# TopView.net
KiCad netlist of a schematic drawn in Altium Designer
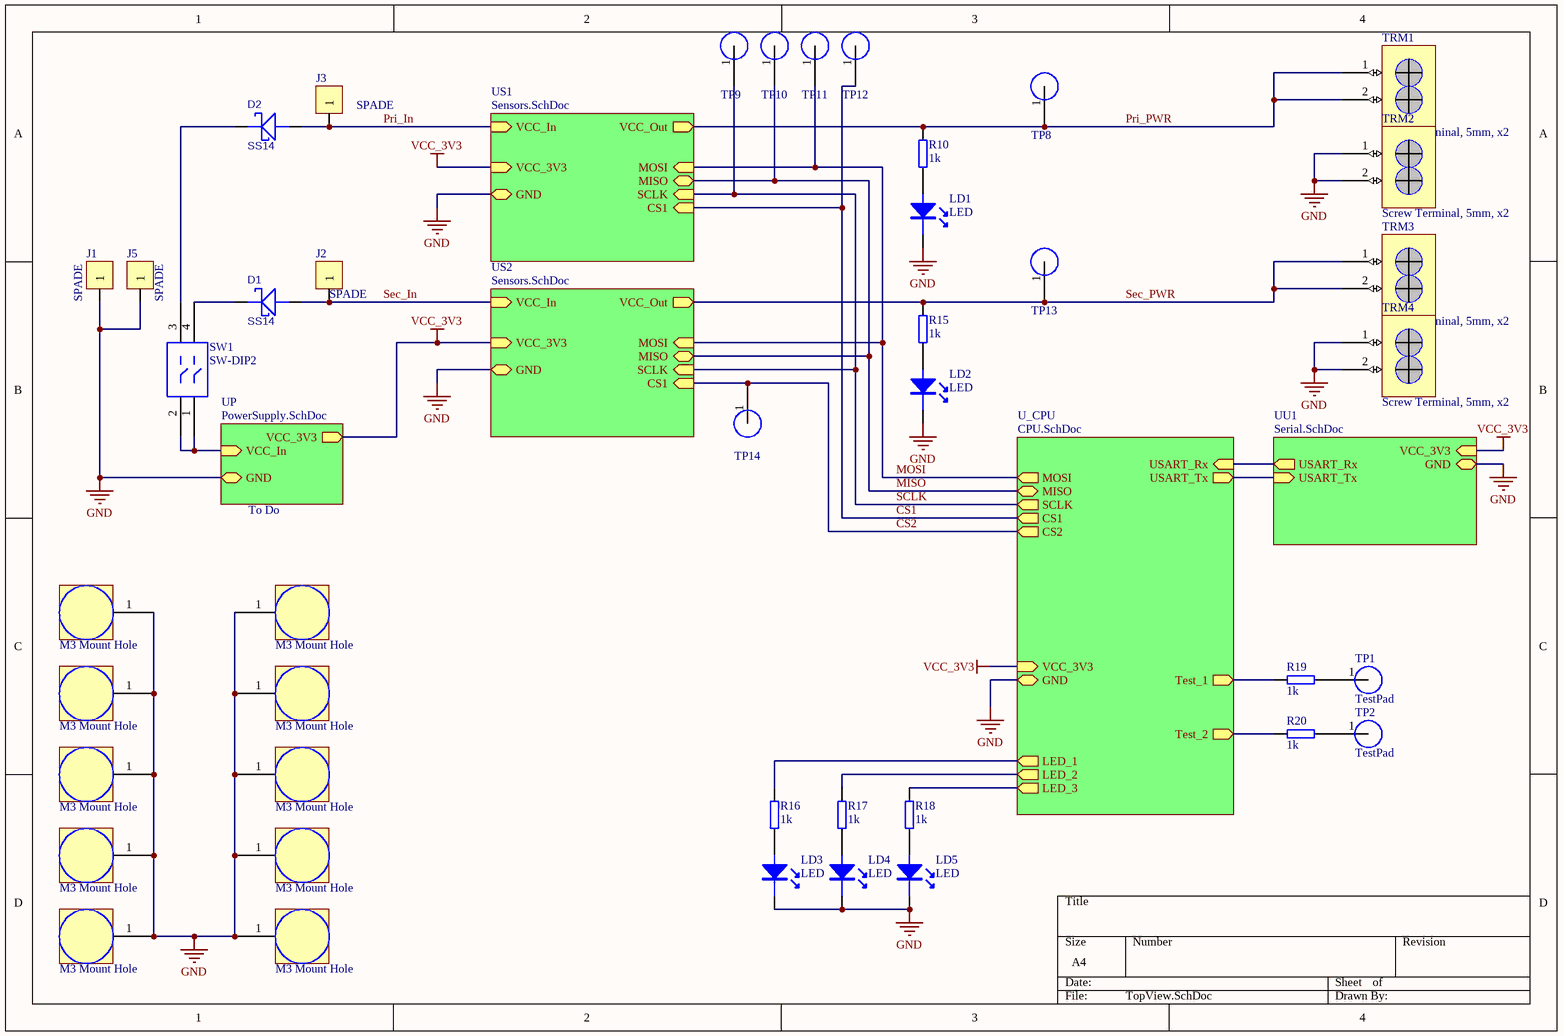
[diagram p0: TopView.SchDoc]

(export (version "E")
  (design (tool "Eeschema 10.0.6"))
  (components
    (comp (ref "D1") (value "SS14") (footprint "DO-214AC") (libsource (lib "DEVICE") (part "DIODE SCHOTTKY")))
    (comp (ref "D2") (value "SS14") (footprint "DO-214AC") (libsource (lib "DEVICE") (part "DIODE SCHOTTKY")))
    (comp (ref "J1") (value "SPADE") (footprint "SPADE6.3-V") (libsource (lib "*") (part "CON1")))
    (comp (ref "J2") (value "SPADE") (footprint "SPADE6.3-V") (libsource (lib "*") (part "CON1")))
    (comp (ref "J3") (value "SPADE") (footprint "SPADE6.3-V") (libsource (lib "*") (part "CON1")))
    (comp (ref "J5") (value "SPADE") (footprint "SPADE6.3-V") (libsource (lib "*") (part "CON1")))
    (comp (ref "LD1") (value "LED") (footprint "LED3") (libsource (lib "DEVICE") (part "LED")))
    (comp (ref "LD2") (value "LED") (footprint "LED3") (libsource (lib "DEVICE") (part "LED")))
    (comp (ref "LD3") (value "LED") (footprint "LED3") (libsource (lib "DEVICE") (part "LED")))
    (comp (ref "LD4") (value "LED") (footprint "LED3") (libsource (lib "DEVICE") (part "LED")))
    (comp (ref "LD5") (value "LED") (footprint "LED3") (libsource (lib "DEVICE") (part "LED")))
    (comp (ref "MNT1")
      (value "M3 Mount Hole")
      (footprint "Mount_M3")
      (libsource (lib "") (part "M3_Mount_1"))
    )
    (comp (ref "MNT2")
      (value "M3 Mount Hole")
      (footprint "Mount_M3")
      (libsource (lib "Hardware") (part "M3_Mount"))
    )
    (comp (ref "MNT3")
      (value "M3 Mount Hole")
      (footprint "Mount_M3")
      (libsource (lib "") (part "M3_Mount_1"))
    )
    (comp (ref "MNT4")
      (value "M3 Mount Hole")
      (footprint "Mount_M3")
      (libsource (lib "Hardware") (part "M3_Mount"))
    )
    (comp (ref "MNT5")
      (value "M3 Mount Hole")
      (footprint "Mount_M3")
      (libsource (lib "") (part "M3_Mount_1"))
    )
    (comp (ref "MNT6")
      (value "M3 Mount Hole")
      (footprint "Mount_M3")
      (libsource (lib "Hardware") (part "M3_Mount"))
    )
    (comp (ref "MNT7")
      (value "M3 Mount Hole")
      (footprint "Mount_M3")
      (libsource (lib "") (part "M3_Mount_1"))
    )
    (comp (ref "MNT8")
      (value "M3 Mount Hole")
      (footprint "Mount_M3")
      (libsource (lib "Hardware") (part "M3_Mount"))
    )
    (comp (ref "MNT9")
      (value "M3 Mount Hole")
      (footprint "Mount_M3")
      (libsource (lib "") (part "M3_Mount_1"))
    )
    (comp (ref "MNT10")
      (value "M3 Mount Hole")
      (footprint "Mount_M3")
      (libsource (lib "Hardware") (part "M3_Mount"))
    )
    (comp (ref "R10") (value "1k") (footprint "0603") (libsource (lib "DEVICE") (part "RES8")))
    (comp (ref "R15") (value "1k") (footprint "0603") (libsource (lib "DEVICE") (part "RES8")))
    (comp (ref "R16") (value "1k") (footprint "0603") (libsource (lib "DEVICE") (part "RES8")))
    (comp (ref "R17") (value "1k") (footprint "0603") (libsource (lib "DEVICE") (part "RES8")))
    (comp (ref "R18") (value "1k") (footprint "0603") (libsource (lib "DEVICE") (part "RES8")))
    (comp (ref "R19") (value "1k") (footprint "0603") (libsource (lib "DEVICE") (part "RES8")))
    (comp (ref "R20") (value "1k") (footprint "0603") (libsource (lib "DEVICE") (part "RES8")))
    (comp (ref "SW1") (value "SW-DIP2") (footprint "DIPSW2") (libsource (lib "DEVICE") (part "SW-DIP2")))
    (comp (ref "TP1")
      (value "TestPad")
      (footprint "TestPad")
      (description "Test Pad")
      (libsource (lib "Hardware") (part "TestPad"))
    )
    (comp (ref "TP2")
      (value "TestPad")
      (footprint "TestPad")
      (description "Test Pad")
      (libsource (lib "Hardware") (part "TestPad"))
    )
    (comp (ref "TP8")
      (value "TestPad")
      (footprint "TestPad")
      (description "Test Pad")
      (libsource (lib "Hardware") (part "TestPad"))
    )
    (comp (ref "TP9")
      (value "TestPad")
      (footprint "TestPad")
      (description "Test Pad")
      (libsource (lib "Hardware") (part "TestPad"))
    )
    (comp (ref "TP10")
      (value "TestPad")
      (footprint "TestPad")
      (description "Test Pad")
      (libsource (lib "Hardware") (part "TestPad"))
    )
    (comp (ref "TP11")
      (value "TestPad")
      (footprint "TestPad")
      (description "Test Pad")
      (libsource (lib "Hardware") (part "TestPad"))
    )
    (comp (ref "TP12")
      (value "TestPad")
      (footprint "TestPad")
      (description "Test Pad")
      (libsource (lib "Hardware") (part "TestPad"))
    )
    (comp (ref "TP13")
      (value "TestPad")
      (footprint "TestPad")
      (description "Test Pad")
      (libsource (lib "Hardware") (part "TestPad"))
    )
    (comp (ref "TP14")
      (value "TestPad")
      (footprint "TestPad")
      (description "Test Pad")
      (libsource (lib "Hardware") (part "TestPad"))
    )
    (comp (ref "TRM1")
      (value "Screw Terminal, 5mm, x2")
      (footprint "Terms5mm2")
      (libsource (lib "Hardware") (part "ScrewTerms5mm2"))
    )
    (comp (ref "TRM2")
      (value "Screw Terminal, 5mm, x2")
      (footprint "Terms5mm2")
      (libsource (lib "Hardware") (part "ScrewTerms5mm2"))
    )
    (comp (ref "TRM3")
      (value "Screw Terminal, 5mm, x2")
      (footprint "Terms5mm2")
      (libsource (lib "Hardware") (part "ScrewTerms5mm2"))
    )
    (comp (ref "TRM4")
      (value "Screw Terminal, 5mm, x2")
      (footprint "Terms5mm2")
      (libsource (lib "Hardware") (part "ScrewTerms5mm2"))
    )
  )
  (nets
    (net (code "1") (name "/CS1") (class "Default") (node (ref "TP12") (pin "1") (pintype "passive")))
    (net (code "2") (name "/CS2") (class "Default") (node (ref "TP14") (pin "1") (pintype "passive")))
    (net (code "3") (name "/LED_1") (class "Default") (node (ref "R16") (pin "2") (pintype "passive")))
    (net (code "4") (name "/LED_2") (class "Default") (node (ref "R17") (pin "2") (pintype "passive")))
    (net (code "5") (name "/LED_3") (class "Default") (node (ref "R18") (pin "2") (pintype "passive")))
    (net (code "6") (name "/MISO") (class "Default") (node (ref "TP10") (pin "1") (pintype "passive")))
    (net (code "7") (name "/MOSI") (class "Default") (node (ref "TP11") (pin "1") (pintype "passive")))
    (net (code "8") (name "/Pri_In") (class "Default")
      (node (ref "D2") (pin "A") (pinfunction "A_A") (pintype "passive"))
      (node (ref "J3") (pin "1") (pinfunction "1_1") (pintype "passive"))
    )
    (net (code "9") (name "/Pri_PWR") (class "Default")
      (node (ref "R10") (pin "2") (pintype "passive"))
      (node (ref "TP8") (pin "1") (pintype "passive"))
      (node (ref "TRM1") (pin "1") (pintype "bidirectional"))
      (node (ref "TRM1") (pin "2") (pintype "bidirectional"))
    )
    (net (code "10") (name "/SCLK") (class "Default") (node (ref "TP9") (pin "1") (pintype "passive")))
    (net (code "11") (name "/Sec_In") (class "Default")
      (node (ref "D1") (pin "A") (pinfunction "A_A") (pintype "passive"))
      (node (ref "J2") (pin "1") (pinfunction "1_1") (pintype "passive"))
    )
    (net (code "12") (name "/Sec_PWR") (class "Default")
      (node (ref "R15") (pin "2") (pintype "passive"))
      (node (ref "TP13") (pin "1") (pintype "passive"))
      (node (ref "TRM3") (pin "1") (pintype "bidirectional"))
      (node (ref "TRM3") (pin "2") (pintype "bidirectional"))
    )
    (net (code "13") (name "/Test_1") (class "Default") (node (ref "R19") (pin "2") (pintype "passive")))
    (net (code "14") (name "/Test_2") (class "Default") (node (ref "R20") (pin "2") (pintype "passive")))
    (net (code "17") (name "/VCC_In") (class "Default")
      (node (ref "SW1") (pin "1") (pintype "passive"))
      (node (ref "SW1") (pin "2") (pintype "passive"))
    )
    (net (code "18") (name "GND") (class "Default")
      (node (ref "J1") (pin "1") (pinfunction "1_1") (pintype "passive"))
      (node (ref "J5") (pin "1") (pinfunction "1_1") (pintype "passive"))
      (node (ref "LD1") (pin "K") (pintype "passive"))
      (node (ref "LD2") (pin "K") (pintype "passive"))
      (node (ref "LD3") (pin "K") (pintype "passive"))
      (node (ref "LD4") (pin "K") (pintype "passive"))
      (node (ref "LD5") (pin "K") (pintype "passive"))
      (node (ref "MNT1") (pin "1") (pintype "passive"))
      (node (ref "MNT10") (pin "1") (pintype "passive"))
      (node (ref "MNT2") (pin "1") (pintype "passive"))
      (node (ref "MNT3") (pin "1") (pintype "passive"))
      (node (ref "MNT4") (pin "1") (pintype "passive"))
      (node (ref "MNT5") (pin "1") (pintype "passive"))
      (node (ref "MNT6") (pin "1") (pintype "passive"))
      (node (ref "MNT7") (pin "1") (pintype "passive"))
      (node (ref "MNT8") (pin "1") (pintype "passive"))
      (node (ref "MNT9") (pin "1") (pintype "passive"))
      (node (ref "TRM2") (pin "1") (pintype "bidirectional"))
      (node (ref "TRM2") (pin "2") (pintype "bidirectional"))
      (node (ref "TRM4") (pin "1") (pintype "bidirectional"))
      (node (ref "TRM4") (pin "2") (pintype "bidirectional"))
    )
    (net (code "19") (name "Net-(D1-PadK)") (class "Default")
      (node (ref "D1") (pin "K") (pinfunction "K_K") (pintype "passive"))
      (node (ref "SW1") (pin "4") (pintype "passive"))
    )
    (net (code "20") (name "Net-(D2-PadK)") (class "Default")
      (node (ref "D2") (pin "K") (pinfunction "K_K") (pintype "passive"))
      (node (ref "SW1") (pin "3") (pintype "passive"))
    )
    (net (code "21") (name "Net-(LD1-PadA)") (class "Default")
      (node (ref "LD1") (pin "A") (pintype "passive"))
      (node (ref "R10") (pin "1") (pintype "passive"))
    )
    (net (code "22") (name "Net-(LD2-PadA)") (class "Default")
      (node (ref "LD2") (pin "A") (pintype "passive"))
      (node (ref "R15") (pin "1") (pintype "passive"))
    )
    (net (code "23") (name "Net-(LD3-PadA)") (class "Default")
      (node (ref "LD3") (pin "A") (pintype "passive"))
      (node (ref "R16") (pin "1") (pintype "passive"))
    )
    (net (code "24") (name "Net-(LD4-PadA)") (class "Default")
      (node (ref "LD4") (pin "A") (pintype "passive"))
      (node (ref "R17") (pin "1") (pintype "passive"))
    )
    (net (code "25") (name "Net-(LD5-PadA)") (class "Default")
      (node (ref "LD5") (pin "A") (pintype "passive"))
      (node (ref "R18") (pin "1") (pintype "passive"))
    )
    (net (code "26") (name "Net-(R19-Pad1)") (class "Default")
      (node (ref "R19") (pin "1") (pintype "passive"))
      (node (ref "TP1") (pin "1") (pintype "passive"))
    )
    (net (code "27") (name "Net-(R20-Pad1)") (class "Default")
      (node (ref "R20") (pin "1") (pintype "passive"))
      (node (ref "TP2") (pin "1") (pintype "passive"))
    )
  )
)
